# FPGA_01.net
KiCad netlist of a schematic drawn in Altium Designer
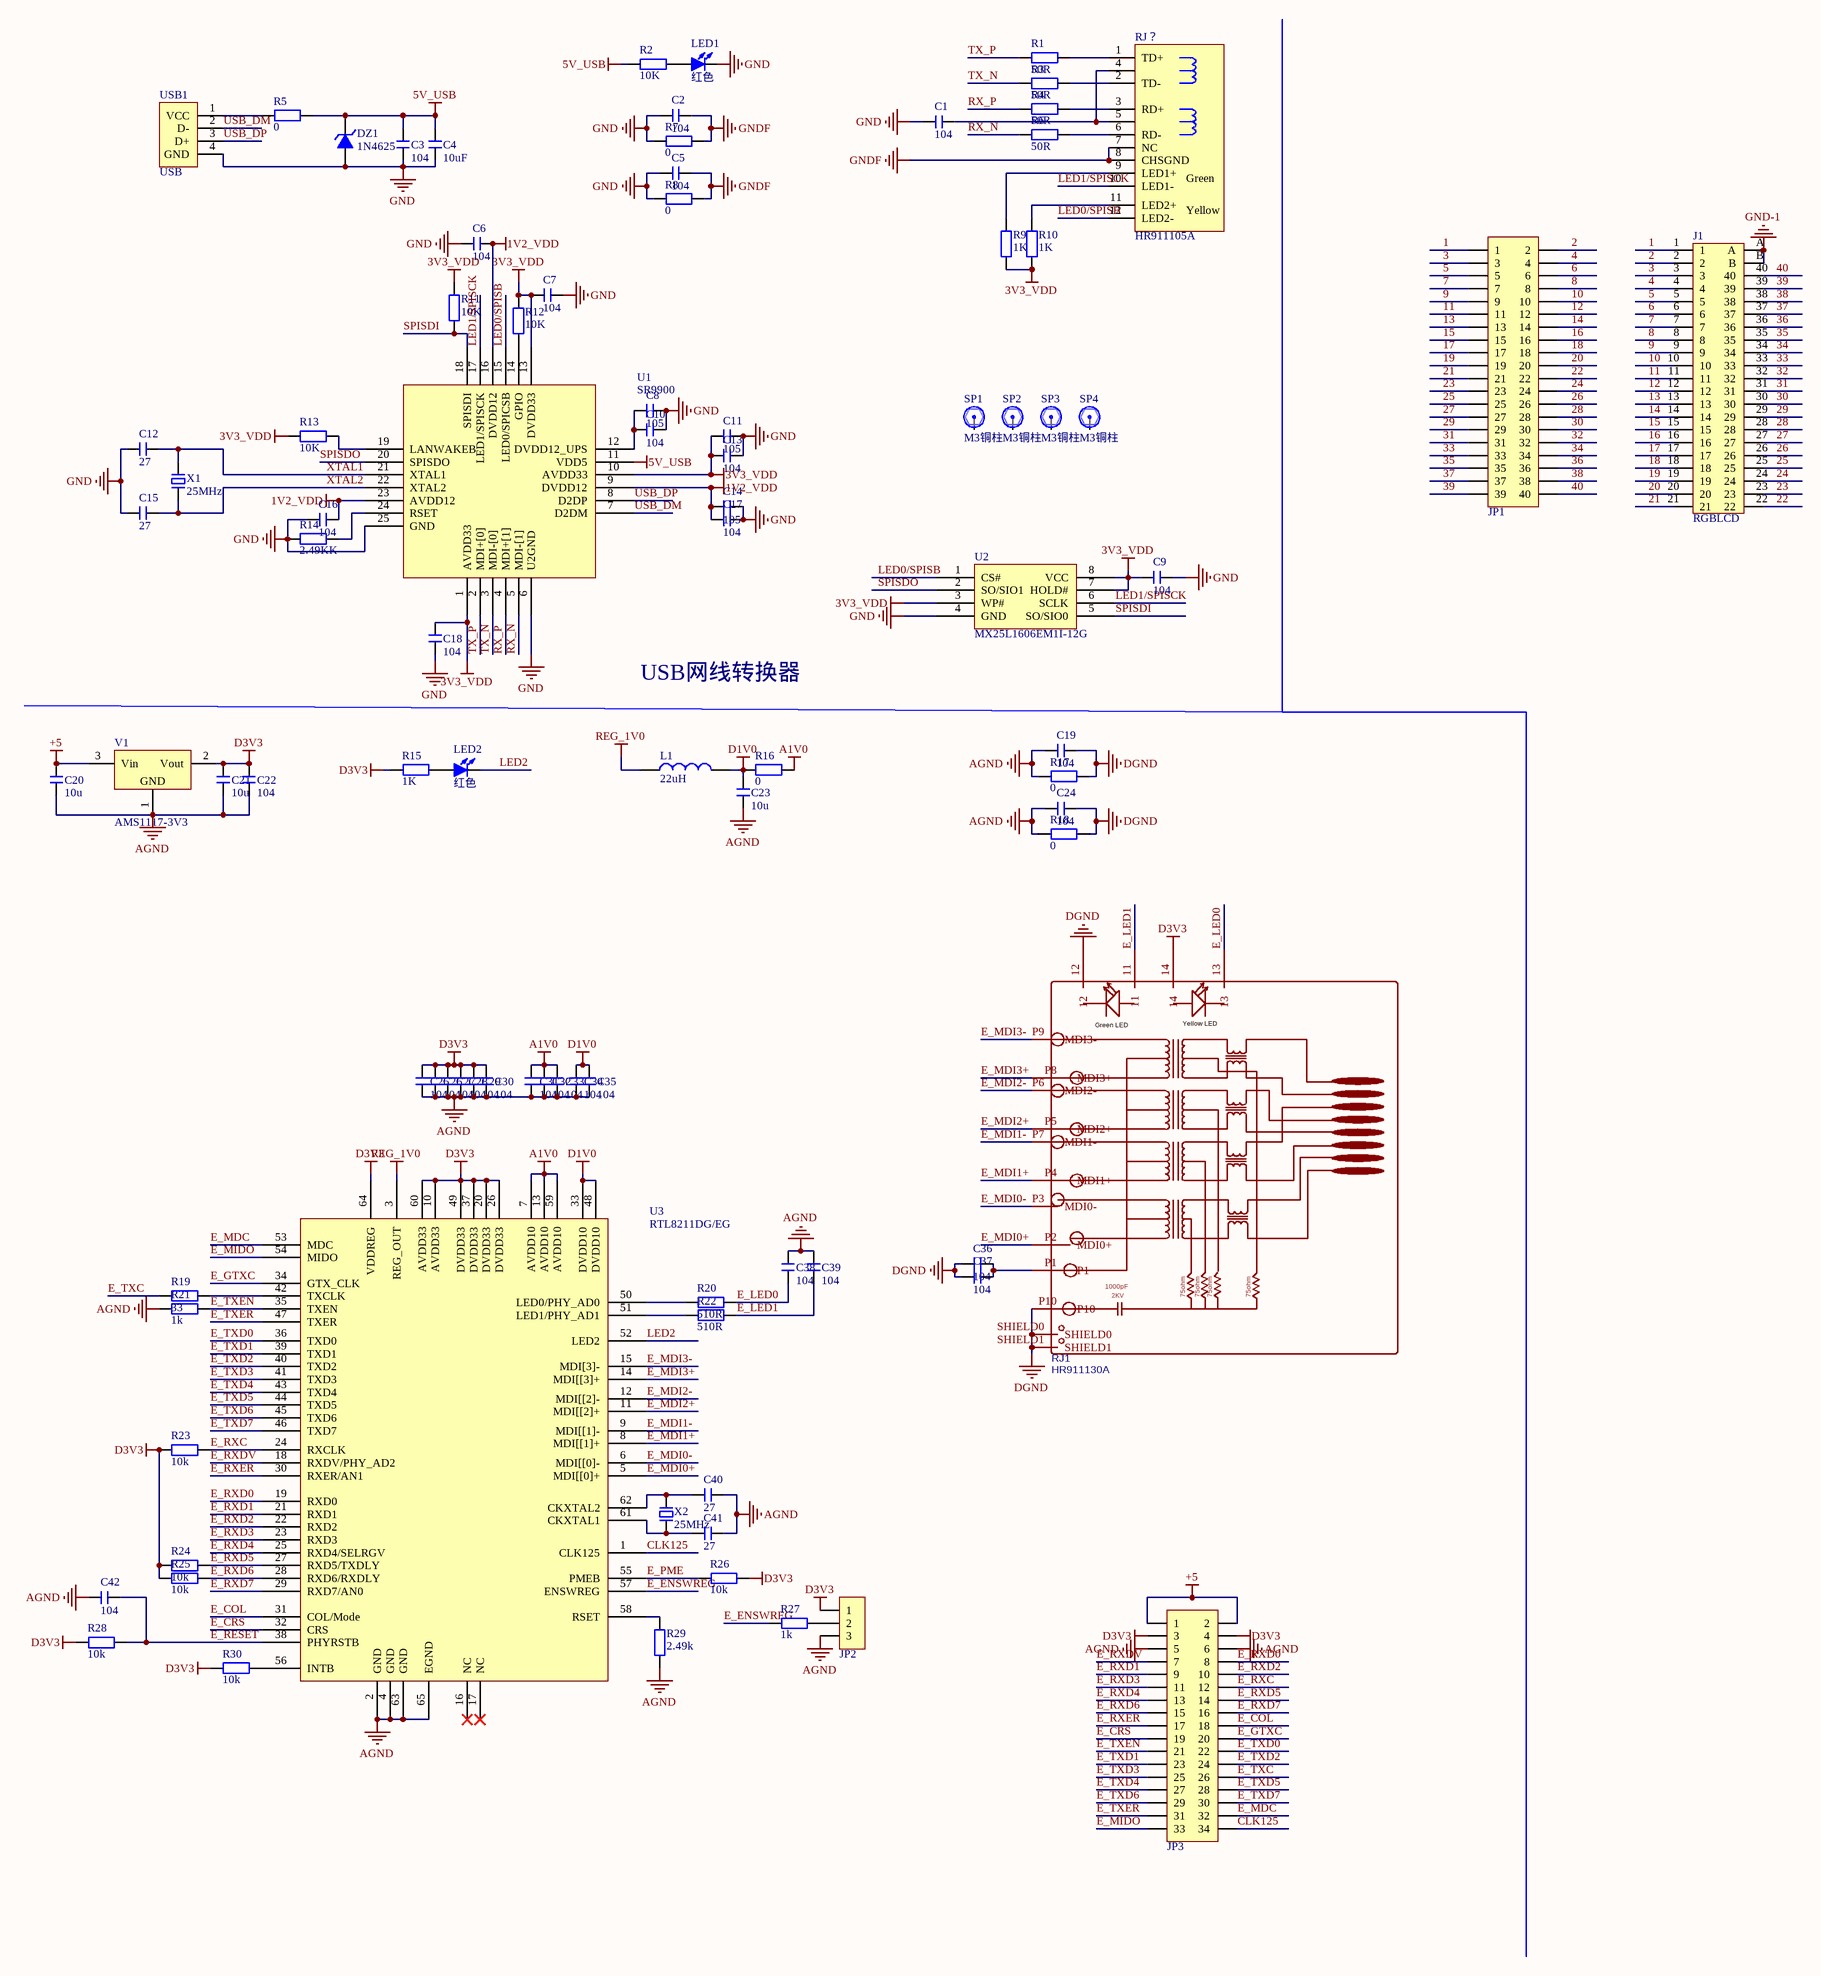
[diagram p0: FPGA扩展板01.SchDoc]

(export (version "E")
  (design (tool "Eeschema 10.0.6"))
  (components
    (comp (ref "C1")
      (value "104")
      (footprint "C 0805_L")
      (description "贴片电容")
      (libsource (lib "0.1 - 电阻-电容-电感") (part "C"))
    )
    (comp (ref "C2")
      (value "104")
      (footprint "C 0805_L")
      (description "贴片电容")
      (libsource (lib "0.1 - 电阻-电容-电感") (part "C"))
    )
    (comp (ref "C3")
      (value "104")
      (footprint "C 0805_L")
      (description "贴片电容")
      (libsource (lib "0.1 - 电阻-电容-电感") (part "C"))
    )
    (comp (ref "C4")
      (value "10uF")
      (footprint "C 0805_L")
      (description "贴片电容")
      (libsource (lib "0.1 - 电阻-电容-电感") (part "C"))
    )
    (comp (ref "C5")
      (value "104")
      (footprint "C 0805_L")
      (description "贴片电容")
      (libsource (lib "0.1 - 电阻-电容-电感") (part "C"))
    )
    (comp (ref "C6")
      (value "104")
      (footprint "C 0805_L")
      (description "贴片电容")
      (libsource (lib "0.1 - 电阻-电容-电感") (part "C"))
    )
    (comp (ref "C7")
      (value "104")
      (footprint "C 0805_L")
      (description "贴片电容")
      (libsource (lib "0.1 - 电阻-电容-电感") (part "C"))
    )
    (comp (ref "C8")
      (value "105")
      (footprint "C 0805_L")
      (description "贴片电容")
      (libsource (lib "0.1 - 电阻-电容-电感") (part "C"))
    )
    (comp (ref "C9")
      (value "104")
      (footprint "C 0805_L")
      (description "贴片电容")
      (libsource (lib "0.1 - 电阻-电容-电感") (part "C"))
    )
    (comp (ref "C10")
      (value "104")
      (footprint "C 0805_L")
      (description "贴片电容")
      (libsource (lib "0.1 - 电阻-电容-电感") (part "C"))
    )
    (comp (ref "C11")
      (value "105")
      (footprint "C 0805_L")
      (description "贴片电容")
      (libsource (lib "0.1 - 电阻-电容-电感") (part "C"))
    )
    (comp (ref "C12")
      (value "27")
      (footprint "C 0805_L")
      (description "贴片电容")
      (libsource (lib "0.1 - 电阻-电容-电感") (part "C"))
    )
    (comp (ref "C13")
      (value "104")
      (footprint "C 0805_L")
      (description "贴片电容")
      (libsource (lib "0.1 - 电阻-电容-电感") (part "C"))
    )
    (comp (ref "C14")
      (value "105")
      (footprint "C 0805_L")
      (description "贴片电容")
      (libsource (lib "0.1 - 电阻-电容-电感") (part "C"))
    )
    (comp (ref "C15")
      (value "27")
      (footprint "C 0805_L")
      (description "贴片电容")
      (libsource (lib "0.1 - 电阻-电容-电感") (part "C"))
    )
    (comp (ref "C16")
      (value "104")
      (footprint "C 0805_L")
      (description "贴片电容")
      (libsource (lib "0.1 - 电阻-电容-电感") (part "C"))
    )
    (comp (ref "C17")
      (value "104")
      (footprint "C 0805_L")
      (description "贴片电容")
      (libsource (lib "0.1 - 电阻-电容-电感") (part "C"))
    )
    (comp (ref "C18")
      (value "104")
      (footprint "C 0805_L")
      (description "贴片电容")
      (libsource (lib "0.1 - 电阻-电容-电感") (part "C"))
    )
    (comp (ref "C19")
      (value "104")
      (footprint "C 0805_L")
      (description "贴片电容")
      (libsource (lib "0.1 - 电阻-电容-电感") (part "C"))
    )
    (comp (ref "C20")
      (value "10u")
      (footprint "C 0805_L")
      (description "贴片电容")
      (libsource (lib "0.1 - 电阻-电容-电感") (part "C"))
    )
    (comp (ref "C21")
      (value "10u")
      (footprint "C 0805_L")
      (description "贴片电容")
      (libsource (lib "0.1 - 电阻-电容-电感") (part "C"))
    )
    (comp (ref "C22")
      (value "104")
      (footprint "C 0805_L")
      (description "贴片电容")
      (libsource (lib "0.1 - 电阻-电容-电感") (part "C"))
    )
    (comp (ref "C23")
      (value "10u")
      (footprint "C 0805_L")
      (description "贴片电容")
      (libsource (lib "0.1 - 电阻-电容-电感") (part "C"))
    )
    (comp (ref "C24")
      (value "104")
      (footprint "C 0805_L")
      (description "贴片电容")
      (libsource (lib "0.1 - 电阻-电容-电感") (part "C"))
    )
    (comp (ref "C25")
      (value "104")
      (footprint "C 0805_L")
      (description "贴片电容")
      (libsource (lib "0.1 - 电阻-电容-电感") (part "C"))
    )
    (comp (ref "C26")
      (value "104")
      (footprint "C 0805_L")
      (description "贴片电容")
      (libsource (lib "0.1 - 电阻-电容-电感") (part "C"))
    )
    (comp (ref "C27")
      (value "104")
      (footprint "C 0805_L")
      (description "贴片电容")
      (libsource (lib "0.1 - 电阻-电容-电感") (part "C"))
    )
    (comp (ref "C28")
      (value "104")
      (footprint "C 0805_L")
      (description "贴片电容")
      (libsource (lib "0.1 - 电阻-电容-电感") (part "C"))
    )
    (comp (ref "C29")
      (value "104")
      (footprint "C 0805_L")
      (description "贴片电容")
      (libsource (lib "0.1 - 电阻-电容-电感") (part "C"))
    )
    (comp (ref "C30")
      (value "104")
      (footprint "C 0805_L")
      (description "贴片电容")
      (libsource (lib "0.1 - 电阻-电容-电感") (part "C"))
    )
    (comp (ref "C31")
      (value "104")
      (footprint "C 0805_L")
      (description "贴片电容")
      (libsource (lib "0.1 - 电阻-电容-电感") (part "C"))
    )
    (comp (ref "C32")
      (value "104")
      (footprint "C 0805_L")
      (description "贴片电容")
      (libsource (lib "0.1 - 电阻-电容-电感") (part "C"))
    )
    (comp (ref "C33")
      (value "104")
      (footprint "C 0805_L")
      (description "贴片电容")
      (libsource (lib "0.1 - 电阻-电容-电感") (part "C"))
    )
    (comp (ref "C34")
      (value "104")
      (footprint "C 0805_L")
      (description "贴片电容")
      (libsource (lib "0.1 - 电阻-电容-电感") (part "C"))
    )
    (comp (ref "C35")
      (value "104")
      (footprint "C 0805_L")
      (description "贴片电容")
      (libsource (lib "0.1 - 电阻-电容-电感") (part "C"))
    )
    (comp (ref "C36")
      (value "104")
      (footprint "C 0805_L")
      (description "贴片电容")
      (libsource (lib "0.1 - 电阻-电容-电感") (part "C"))
    )
    (comp (ref "C37")
      (value "104")
      (footprint "C 0805_L")
      (description "贴片电容")
      (libsource (lib "0.1 - 电阻-电容-电感") (part "C"))
    )
    (comp (ref "C38")
      (value "104")
      (footprint "C 0805_L")
      (description "贴片电容")
      (libsource (lib "0.1 - 电阻-电容-电感") (part "C"))
    )
    (comp (ref "C39")
      (value "104")
      (footprint "C 0805_L")
      (description "贴片电容")
      (libsource (lib "0.1 - 电阻-电容-电感") (part "C"))
    )
    (comp (ref "C40")
      (value "27")
      (footprint "C 0805_L")
      (description "贴片电容")
      (libsource (lib "0.1 - 电阻-电容-电感") (part "C"))
    )
    (comp (ref "C41")
      (value "27")
      (footprint "C 0805_L")
      (description "贴片电容")
      (libsource (lib "0.1 - 电阻-电容-电感") (part "C"))
    )
    (comp (ref "C42")
      (value "104")
      (footprint "C 0805_L")
      (description "贴片电容")
      (libsource (lib "0.1 - 电阻-电容-电感") (part "C"))
    )
    (comp (ref "DZ1")
      (value "1N4625")
      (footprint "DO-35")
      (description "5.1V/0.5W稳压管")
      (libsource (lib "0.2 -  二极管-整流桥") (part "1N4625"))
    )
    (comp (ref "J1")
      (value "RGBLCD")
      (footprint "FPC-TOP40")
      (description "FPC-40P-0.5mm")
      (libsource (lib "PIONEER") (part "FPC-40"))
    )
    (comp (ref "JP1")
      (value "Header 2X11")
      (footprint "HDR2.54-LI-2x20P")
      (description "20*2P接插件")
      (libsource (lib "5.3 - 接插件-脚距2.54 (100mil) ") (part "Header 20X2"))
    )
    (comp (ref "JP2")
      (value "HDR-1X3")
      (footprint "HDR2.54-LI-3P")
      (description "3P接插件")
      (libsource (lib "5.3 - 接插件-脚距2.54 (100mil) ") (part "Header 3"))
    )
    (comp (ref "JP3")
      (value "Header 2X11")
      (footprint "HDR2.54-LI-2x17P")
      (description "17*2P接插件")
      (libsource (lib "5.3 - 接插件-脚距2.54 (100mil) ") (part "Header 17X2"))
    )
    (comp (ref "L1")
      (value "22uH")
      (footprint "L 0805")
      (description "小功率贴片电感")
      (libsource (lib "0.1 - 电阻-电容-电感") (part "L"))
    )
    (comp (ref "LED1")
      (value "红色")
      (footprint "LED 0805G")
      (description "贴片LED")
      (libsource (lib "0.3 - LED发光二极管") (part "LED-SMD"))
    )
    (comp (ref "LED2")
      (value "红色")
      (footprint "LED 0805G")
      (description "贴片LED")
      (libsource (lib "0.3 - LED发光二极管") (part "LED-SMD"))
    )
    (comp (ref "R1")
      (value "50R")
      (footprint "R 0805_L")
      (description "贴片电阻")
      (libsource (lib "0.1 - 电阻-电容-电感") (part "R"))
    )
    (comp (ref "R2")
      (value "10K")
      (footprint "R 0805_L")
      (description "贴片电阻")
      (libsource (lib "0.1 - 电阻-电容-电感") (part "R"))
    )
    (comp (ref "R3")
      (value "50R")
      (footprint "R 0805_L")
      (description "贴片电阻")
      (libsource (lib "0.1 - 电阻-电容-电感") (part "R"))
    )
    (comp (ref "R4")
      (value "50R")
      (footprint "R 0805_L")
      (description "贴片电阻")
      (libsource (lib "0.1 - 电阻-电容-电感") (part "R"))
    )
    (comp (ref "R5")
      (value "0")
      (footprint "R 0805_L")
      (description "贴片电阻")
      (libsource (lib "0.1 - 电阻-电容-电感") (part "R"))
    )
    (comp (ref "R6")
      (value "50R")
      (footprint "R 0805_L")
      (description "贴片电阻")
      (libsource (lib "0.1 - 电阻-电容-电感") (part "R"))
    )
    (comp (ref "R7")
      (value "0")
      (footprint "R 0805_L")
      (description "贴片电阻")
      (libsource (lib "0.1 - 电阻-电容-电感") (part "R"))
    )
    (comp (ref "R8")
      (value "0")
      (footprint "R 0805_L")
      (description "贴片电阻")
      (libsource (lib "0.1 - 电阻-电容-电感") (part "R"))
    )
    (comp (ref "R9")
      (value "1K")
      (footprint "R 0805_L")
      (description "贴片电阻")
      (libsource (lib "0.1 - 电阻-电容-电感") (part "R"))
    )
    (comp (ref "R10")
      (value "1K")
      (footprint "R 0805_L")
      (description "贴片电阻")
      (libsource (lib "0.1 - 电阻-电容-电感") (part "R"))
    )
    (comp (ref "R11")
      (value "10K")
      (footprint "R 0805_L")
      (description "贴片电阻")
      (libsource (lib "0.1 - 电阻-电容-电感") (part "R"))
    )
    (comp (ref "R12")
      (value "10K")
      (footprint "R 0805_L")
      (description "贴片电阻")
      (libsource (lib "0.1 - 电阻-电容-电感") (part "R"))
    )
    (comp (ref "R13")
      (value "10K")
      (footprint "R 0805_L")
      (description "贴片电阻")
      (libsource (lib "0.1 - 电阻-电容-电感") (part "R"))
    )
    (comp (ref "R14")
      (value "2.49KK")
      (footprint "R 0805_L")
      (description "贴片电阻")
      (libsource (lib "0.1 - 电阻-电容-电感") (part "R"))
    )
    (comp (ref "R15")
      (value "1K")
      (footprint "R 0805_L")
      (description "贴片电阻")
      (libsource (lib "0.1 - 电阻-电容-电感") (part "R"))
    )
    (comp (ref "R16")
      (value "0")
      (footprint "R 0805_L")
      (description "贴片电阻")
      (libsource (lib "0.1 - 电阻-电容-电感") (part "R"))
    )
    (comp (ref "R17")
      (value "0")
      (footprint "R 0805_L")
      (description "贴片电阻")
      (libsource (lib "0.1 - 电阻-电容-电感") (part "R"))
    )
    (comp (ref "R18")
      (value "0")
      (footprint "R 0805_L")
      (description "贴片电阻")
      (libsource (lib "0.1 - 电阻-电容-电感") (part "R"))
    )
    (comp (ref "R19")
      (value "33")
      (footprint "R 0805_L")
      (description "贴片电阻")
      (libsource (lib "0.1 - 电阻-电容-电感") (part "R"))
    )
    (comp (ref "R20")
      (value "510R")
      (footprint "R 0805_L")
      (description "贴片电阻")
      (libsource (lib "0.1 - 电阻-电容-电感") (part "R"))
    )
    (comp (ref "R21")
      (value "1k")
      (footprint "R 0805_L")
      (description "贴片电阻")
      (libsource (lib "0.1 - 电阻-电容-电感") (part "R"))
    )
    (comp (ref "R22")
      (value "510R")
      (footprint "R 0805_L")
      (description "贴片电阻")
      (libsource (lib "0.1 - 电阻-电容-电感") (part "R"))
    )
    (comp (ref "R23")
      (value "10k")
      (footprint "R 0805_L")
      (description "贴片电阻")
      (libsource (lib "0.1 - 电阻-电容-电感") (part "R"))
    )
    (comp (ref "R24")
      (value "10k")
      (footprint "R 0805_L")
      (description "贴片电阻")
      (libsource (lib "0.1 - 电阻-电容-电感") (part "R"))
    )
    (comp (ref "R25")
      (value "10k")
      (footprint "R 0805_L")
      (description "贴片电阻")
      (libsource (lib "0.1 - 电阻-电容-电感") (part "R"))
    )
    (comp (ref "R26")
      (value "10k")
      (footprint "R 0805_L")
      (description "贴片电阻")
      (libsource (lib "0.1 - 电阻-电容-电感") (part "R"))
    )
    (comp (ref "R27")
      (value "1k")
      (footprint "R 0805_L")
      (description "贴片电阻")
      (libsource (lib "0.1 - 电阻-电容-电感") (part "R"))
    )
    (comp (ref "R28")
      (value "10k")
      (footprint "R 0805_L")
      (description "贴片电阻")
      (libsource (lib "0.1 - 电阻-电容-电感") (part "R"))
    )
    (comp (ref "R29")
      (value "2.49k")
      (footprint "R 0805_L")
      (description "贴片电阻")
      (libsource (lib "0.1 - 电阻-电容-电感") (part "R"))
    )
    (comp (ref "R30")
      (value "10k")
      (footprint "R 0805_L")
      (description "贴片电阻")
      (libsource (lib "0.1 - 电阻-电容-电感") (part "R"))
    )
    (comp (ref "RJ1")
      (value "HR911130A")
      (footprint "RJ_45")
      (description "RJ_45网口")
      (fields (field (name "BOM_SUPPLIER PART") "C54408"))
      (libsource (lib "Schlib1") (part "HR911130A"))
    )
    (comp (ref "RJ？")
      (value "HR911105A")
      (footprint "RJ-45A12")
      (description "带灯以太网接口")
      (libsource (lib "0.8 - 网口-音频插座") (part "HR911105A"))
    )
    (comp (ref "SP1")
      (value "M3铜柱")
      (footprint "M3x10+6_L")
      (description "铜柱")
      (libsource (lib "4.1 - 未分类器件") (part "铜柱加头小焊盘"))
    )
    (comp (ref "SP2")
      (value "M3铜柱")
      (footprint "M3x10+6_L")
      (description "铜柱")
      (libsource (lib "4.1 - 未分类器件") (part "铜柱加头小焊盘"))
    )
    (comp (ref "SP3")
      (value "M3铜柱")
      (footprint "M3x10+6_L")
      (description "铜柱")
      (libsource (lib "4.1 - 未分类器件") (part "铜柱加头小焊盘"))
    )
    (comp (ref "SP4")
      (value "M3铜柱")
      (footprint "M3x10+6_L")
      (description "铜柱")
      (libsource (lib "4.1 - 未分类器件") (part "铜柱加头小焊盘"))
    )
    (comp (ref "U1") (value "SR9900") (footprint "QFN24 4x4_M") (libsource (lib "Schlib1") (part "SR9900")))
    (comp (ref "U2")
      (value "MX25L1606EM1I-12G")
      (footprint "SOP8W_N")
      (libsource (lib "Schlib1") (part "MX25L1606EM1I-12G"))
    )
    (comp (ref "U3")
      (value "RTL8211DG/EG")
      (footprint "QFN65-050-0909")
      (libsource (lib "Schlib1") (part "RTL8211DG/EG"))
    )
    (comp (ref "USB1")
      (value "USB")
      (footprint "USB_A/P_A")
      (description "USB-A型公接口")
      (libsource (lib "0.8 - 网口-音频插座") (part "USB-A/P"))
    )
    (comp (ref "V1")
      (value "AMS1117-3V3")
      (footprint "SOT223_L")
      (description "三端稳压芯片")
      (libsource (lib "1.1 - 电源类芯片") (part "AMS1117"))
    )
    (comp (ref "X1")
      (value "25MHz")
      (footprint "OSC HC-49S")
      (description "2脚无源脚晶振")
      (libsource (lib "2.0 - 保险丝-晶振-光耦") (part "XTAL-2P"))
    )
    (comp (ref "X2")
      (value "25MHz")
      (footprint "OSC HC-49S")
      (description "2脚无源脚晶振")
      (libsource (lib "2.0 - 保险丝-晶振-光耦") (part "XTAL-2P"))
    )
  )
  (nets
    (net (code "1") (name "+5") (class "Default")
      (node (ref "C20") (pin "2") (pinfunction "2_2") (pintype "passive"))
      (node (ref "JP3") (pin "1") (pinfunction "1_1") (pintype "passive"))
      (node (ref "JP3") (pin "2") (pinfunction "2_2") (pintype "passive"))
      (node (ref "V1") (pin "3") (pinfunction "Vin_3") (pintype "passive"))
    )
    (net (code "2") (name "/1") (class "Default")
      (node (ref "J1") (pin "1") (pinfunction "1_1") (pintype "passive"))
      (node (ref "JP1") (pin "1") (pinfunction "1_1") (pintype "passive"))
    )
    (net (code "3") (name "/2") (class "Default")
      (node (ref "J1") (pin "2") (pinfunction "2_2") (pintype "passive"))
      (node (ref "JP1") (pin "2") (pinfunction "2_2") (pintype "passive"))
    )
    (net (code "4") (name "/3") (class "Default")
      (node (ref "J1") (pin "3") (pinfunction "3_3") (pintype "passive"))
      (node (ref "JP1") (pin "3") (pinfunction "3_3") (pintype "passive"))
    )
    (net (code "5") (name "/4") (class "Default")
      (node (ref "J1") (pin "4") (pinfunction "4_4") (pintype "passive"))
      (node (ref "JP1") (pin "4") (pinfunction "4_4") (pintype "passive"))
    )
    (net (code "6") (name "/5") (class "Default")
      (node (ref "J1") (pin "5") (pinfunction "5_5") (pintype "passive"))
      (node (ref "JP1") (pin "5") (pinfunction "5_5") (pintype "passive"))
    )
    (net (code "7") (name "/6") (class "Default")
      (node (ref "J1") (pin "6") (pinfunction "6_6") (pintype "passive"))
      (node (ref "JP1") (pin "6") (pinfunction "6_6") (pintype "passive"))
    )
    (net (code "8") (name "/7") (class "Default")
      (node (ref "J1") (pin "7") (pinfunction "7_7") (pintype "passive"))
      (node (ref "JP1") (pin "7") (pinfunction "7_7") (pintype "passive"))
    )
    (net (code "9") (name "/8") (class "Default")
      (node (ref "J1") (pin "8") (pinfunction "8_8") (pintype "passive"))
      (node (ref "JP1") (pin "8") (pinfunction "8_8") (pintype "passive"))
    )
    (net (code "10") (name "/9") (class "Default")
      (node (ref "J1") (pin "9") (pinfunction "9_9") (pintype "passive"))
      (node (ref "JP1") (pin "9") (pinfunction "9_9") (pintype "passive"))
    )
    (net (code "11") (name "/10") (class "Default")
      (node (ref "J1") (pin "10") (pinfunction "10_10") (pintype "passive"))
      (node (ref "JP1") (pin "10") (pinfunction "10_10") (pintype "passive"))
    )
    (net (code "12") (name "/11") (class "Default")
      (node (ref "J1") (pin "11") (pinfunction "11_11") (pintype "passive"))
      (node (ref "JP1") (pin "11") (pinfunction "11_11") (pintype "passive"))
    )
    (net (code "13") (name "/12") (class "Default")
      (node (ref "J1") (pin "12") (pinfunction "12_12") (pintype "passive"))
      (node (ref "JP1") (pin "12") (pinfunction "12_12") (pintype "passive"))
    )
    (net (code "14") (name "/13") (class "Default")
      (node (ref "J1") (pin "13") (pinfunction "13_13") (pintype "passive"))
      (node (ref "JP1") (pin "13") (pinfunction "13_13") (pintype "passive"))
    )
    (net (code "15") (name "/14") (class "Default")
      (node (ref "J1") (pin "14") (pinfunction "14_14") (pintype "passive"))
      (node (ref "JP1") (pin "14") (pinfunction "14_14") (pintype "passive"))
    )
    (net (code "16") (name "/15") (class "Default")
      (node (ref "J1") (pin "15") (pinfunction "15_15") (pintype "passive"))
      (node (ref "JP1") (pin "15") (pinfunction "15_15") (pintype "passive"))
    )
    (net (code "17") (name "/16") (class "Default")
      (node (ref "J1") (pin "16") (pinfunction "16_16") (pintype "passive"))
      (node (ref "JP1") (pin "16") (pinfunction "16_16") (pintype "passive"))
    )
    (net (code "18") (name "/17") (class "Default")
      (node (ref "J1") (pin "17") (pinfunction "17_17") (pintype "passive"))
      (node (ref "JP1") (pin "17") (pinfunction "17_17") (pintype "passive"))
    )
    (net (code "19") (name "/18") (class "Default")
      (node (ref "J1") (pin "18") (pinfunction "18_18") (pintype "passive"))
      (node (ref "JP1") (pin "18") (pinfunction "18_18") (pintype "passive"))
    )
    (net (code "20") (name "/19") (class "Default")
      (node (ref "J1") (pin "19") (pinfunction "19_19") (pintype "passive"))
      (node (ref "JP1") (pin "19") (pinfunction "19_19") (pintype "passive"))
    )
    (net (code "21") (name "/20") (class "Default")
      (node (ref "J1") (pin "20") (pinfunction "20_20") (pintype "passive"))
      (node (ref "JP1") (pin "20") (pinfunction "20_20") (pintype "passive"))
    )
    (net (code "22") (name "/21") (class "Default")
      (node (ref "J1") (pin "21") (pinfunction "21_21") (pintype "passive"))
      (node (ref "JP1") (pin "21") (pinfunction "21_21") (pintype "passive"))
    )
    (net (code "23") (name "/22") (class "Default")
      (node (ref "J1") (pin "22") (pinfunction "22_22") (pintype "passive"))
      (node (ref "JP1") (pin "22") (pinfunction "22_22") (pintype "passive"))
    )
    (net (code "24") (name "/23") (class "Default")
      (node (ref "J1") (pin "23") (pinfunction "23_23") (pintype "passive"))
      (node (ref "JP1") (pin "23") (pinfunction "23_23") (pintype "passive"))
    )
    (net (code "25") (name "/24") (class "Default")
      (node (ref "J1") (pin "24") (pinfunction "24_24") (pintype "passive"))
      (node (ref "JP1") (pin "24") (pinfunction "24_24") (pintype "passive"))
    )
    (net (code "26") (name "/25") (class "Default")
      (node (ref "J1") (pin "25") (pinfunction "25_25") (pintype "passive"))
      (node (ref "JP1") (pin "25") (pinfunction "25_25") (pintype "passive"))
    )
    (net (code "27") (name "/26") (class "Default")
      (node (ref "J1") (pin "26") (pinfunction "26_26") (pintype "passive"))
      (node (ref "JP1") (pin "26") (pinfunction "26_26") (pintype "passive"))
    )
    (net (code "28") (name "/27") (class "Default")
      (node (ref "J1") (pin "27") (pinfunction "27_27") (pintype "passive"))
      (node (ref "JP1") (pin "27") (pinfunction "27_27") (pintype "passive"))
    )
    (net (code "29") (name "/28") (class "Default")
      (node (ref "J1") (pin "28") (pinfunction "28_28") (pintype "passive"))
      (node (ref "JP1") (pin "28") (pinfunction "28_28") (pintype "passive"))
    )
    (net (code "30") (name "/29") (class "Default")
      (node (ref "J1") (pin "29") (pinfunction "29_29") (pintype "passive"))
      (node (ref "JP1") (pin "29") (pinfunction "29_29") (pintype "passive"))
    )
    (net (code "31") (name "/30") (class "Default")
      (node (ref "J1") (pin "30") (pinfunction "30_30") (pintype "passive"))
      (node (ref "JP1") (pin "30") (pinfunction "30_30") (pintype "passive"))
    )
    (net (code "32") (name "/31") (class "Default")
      (node (ref "J1") (pin "31") (pinfunction "31_31") (pintype "passive"))
      (node (ref "JP1") (pin "31") (pinfunction "31_31") (pintype "passive"))
    )
    (net (code "33") (name "/32") (class "Default")
      (node (ref "J1") (pin "32") (pinfunction "32_32") (pintype "passive"))
      (node (ref "JP1") (pin "32") (pinfunction "32_32") (pintype "passive"))
    )
    (net (code "34") (name "/33") (class "Default")
      (node (ref "J1") (pin "33") (pinfunction "33_33") (pintype "passive"))
      (node (ref "JP1") (pin "33") (pinfunction "33_33") (pintype "passive"))
    )
    (net (code "35") (name "/34") (class "Default")
      (node (ref "J1") (pin "34") (pinfunction "34_34") (pintype "passive"))
      (node (ref "JP1") (pin "34") (pinfunction "34_34") (pintype "passive"))
    )
    (net (code "36") (name "/35") (class "Default")
      (node (ref "J1") (pin "35") (pinfunction "35_35") (pintype "passive"))
      (node (ref "JP1") (pin "35") (pinfunction "35_35") (pintype "passive"))
    )
    (net (code "37") (name "/36") (class "Default")
      (node (ref "J1") (pin "36") (pinfunction "36_36") (pintype "passive"))
      (node (ref "JP1") (pin "36") (pinfunction "36_36") (pintype "passive"))
    )
    (net (code "38") (name "/37") (class "Default")
      (node (ref "J1") (pin "37") (pinfunction "37_37") (pintype "passive"))
      (node (ref "JP1") (pin "37") (pinfunction "37_37") (pintype "passive"))
    )
    (net (code "39") (name "/38") (class "Default")
      (node (ref "J1") (pin "38") (pinfunction "38_38") (pintype "passive"))
      (node (ref "JP1") (pin "38") (pinfunction "38_38") (pintype "passive"))
    )
    (net (code "40") (name "/39") (class "Default")
      (node (ref "J1") (pin "39") (pinfunction "39_39") (pintype "passive"))
      (node (ref "JP1") (pin "39") (pinfunction "39_39") (pintype "passive"))
    )
    (net (code "41") (name "/40") (class "Default")
      (node (ref "J1") (pin "40") (pinfunction "40_40") (pintype "passive"))
      (node (ref "JP1") (pin "40") (pinfunction "40_40") (pintype "passive"))
    )
    (net (code "42") (name "/CLK125") (class "Default")
      (node (ref "JP3") (pin "34") (pinfunction "34_34") (pintype "passive"))
      (node (ref "U3") (pin "1") (pinfunction "CLK125_1") (pintype "passive"))
    )
    (net (code "43") (name "/E_COL") (class "Default")
      (node (ref "JP3") (pin "18") (pinfunction "18_18") (pintype "passive"))
      (node (ref "U3") (pin "31") (pinfunction "COL/Mode_31") (pintype "passive"))
    )
    (net (code "44") (name "/E_CRS") (class "Default")
      (node (ref "JP3") (pin "19") (pinfunction "19_19") (pintype "passive"))
      (node (ref "U3") (pin "32") (pinfunction "CRS_32") (pintype "passive"))
    )
    (net (code "45") (name "/E_ENSWREG") (class "Default")
      (node (ref "R27") (pin "2") (pinfunction "2_2") (pintype "passive"))
      (node (ref "U3") (pin "57") (pinfunction "ENSWREG_57") (pintype "passive"))
    )
    (net (code "46") (name "/E_GTXC") (class "Default")
      (node (ref "JP3") (pin "20") (pinfunction "20_20") (pintype "passive"))
      (node (ref "U3") (pin "34") (pinfunction "GTX_CLK_34") (pintype "passive"))
    )
    (net (code "47") (name "/E_LED0") (class "Default")
      (node (ref "C38") (pin "1") (pinfunction "1_1") (pintype "passive"))
      (node (ref "R20") (pin "2") (pinfunction "2_2") (pintype "passive"))
      (node (ref "RJ1") (pin "13") (pinfunction "13_13") (pintype "passive"))
    )
    (net (code "48") (name "/E_LED1") (class "Default")
      (node (ref "C39") (pin "1") (pinfunction "1_1") (pintype "passive"))
      (node (ref "R22") (pin "2") (pinfunction "2_2") (pintype "passive"))
      (node (ref "RJ1") (pin "11") (pinfunction "11_11") (pintype "passive"))
    )
    (net (code "49") (name "/E_MDC") (class "Default")
      (node (ref "JP3") (pin "32") (pinfunction "32_32") (pintype "passive"))
      (node (ref "U3") (pin "53") (pinfunction "MDC_53") (pintype "passive"))
    )
    (net (code "50") (name "/E_MDI0+") (class "Default")
      (node (ref "RJ1") (pin "P2") (pinfunction "MDI0+_P2") (pintype "passive"))
      (node (ref "U3") (pin "5") (pinfunction "MDI[[0]+_5") (pintype "passive"))
    )
    (net (code "51") (name "/E_MDI0-") (class "Default")
      (node (ref "RJ1") (pin "P3") (pinfunction "MDI0-_P3") (pintype "passive"))
      (node (ref "U3") (pin "6") (pinfunction "MDI[[0]-_6") (pintype "passive"))
    )
    (net (code "52") (name "/E_MDI1+") (class "Default")
      (node (ref "RJ1") (pin "P4") (pinfunction "MDI1+_P4") (pintype "passive"))
      (node (ref "U3") (pin "8") (pinfunction "MDI[[1]+_8") (pintype "passive"))
    )
    (net (code "53") (name "/E_MDI1-") (class "Default")
      (node (ref "RJ1") (pin "P7") (pinfunction "MDI1-_P7") (pintype "passive"))
      (node (ref "U3") (pin "9") (pinfunction "MDI[[1]-_9") (pintype "passive"))
    )
    (net (code "54") (name "/E_MDI2+") (class "Default")
      (node (ref "RJ1") (pin "P5") (pinfunction "MDI2+_P5") (pintype "passive"))
      (node (ref "U3") (pin "11") (pinfunction "MDI[[2]+_11") (pintype "passive"))
    )
    (net (code "55") (name "/E_MDI2-") (class "Default")
      (node (ref "RJ1") (pin "P6") (pinfunction "MDI2-_P6") (pintype "passive"))
      (node (ref "U3") (pin "12") (pinfunction "MDI[[2]-_12") (pintype "passive"))
    )
    (net (code "56") (name "/E_MDI3+") (class "Default")
      (node (ref "RJ1") (pin "P8") (pinfunction "MDI3+_P8") (pintype "passive"))
      (node (ref "U3") (pin "14") (pinfunction "MDI[[3]+_14") (pintype "passive"))
    )
    (net (code "57") (name "/E_MDI3-") (class "Default")
      (node (ref "RJ1") (pin "P9") (pinfunction "MDI3-_P9") (pintype "passive"))
      (node (ref "U3") (pin "15") (pinfunction "MDI[3]-_15") (pintype "passive"))
    )
    (net (code "58") (name "/E_MIDO") (class "Default")
      (node (ref "JP3") (pin "33") (pinfunction "33_33") (pintype "passive"))
      (node (ref "U3") (pin "54") (pinfunction "MIDO_54") (pintype "passive"))
    )
    (net (code "59") (name "/E_PME") (class "Default")
      (node (ref "R26") (pin "2") (pinfunction "2_2") (pintype "passive"))
      (node (ref "U3") (pin "55") (pinfunction "PMEB_55") (pintype "passive"))
    )
    (net (code "60") (name "/E_RESET") (class "Default")
      (node (ref "C42") (pin "1") (pinfunction "1_1") (pintype "passive"))
      (node (ref "R28") (pin "2") (pinfunction "2_2") (pintype "passive"))
      (node (ref "U3") (pin "38") (pinfunction "PHYRSTB_38") (pintype "passive"))
    )
    (net (code "61") (name "/E_RXC") (class "Default")
      (node (ref "JP3") (pin "12") (pinfunction "12_12") (pintype "passive"))
      (node (ref "R23") (pin "2") (pinfunction "2_2") (pintype "passive"))
      (node (ref "U3") (pin "24") (pinfunction "RXCLK_24") (pintype "passive"))
    )
    (net (code "62") (name "/E_RXD0") (class "Default")
      (node (ref "JP3") (pin "8") (pinfunction "8_8") (pintype "passive"))
      (node (ref "U3") (pin "19") (pinfunction "RXD0_19") (pintype "passive"))
    )
    (net (code "63") (name "/E_RXD1") (class "Default")
      (node (ref "JP3") (pin "9") (pinfunction "9_9") (pintype "passive"))
      (node (ref "U3") (pin "21") (pinfunction "RXD1_21") (pintype "passive"))
    )
    (net (code "64") (name "/E_RXD2") (class "Default")
      (node (ref "JP3") (pin "10") (pinfunction "10_10") (pintype "passive"))
      (node (ref "U3") (pin "22") (pinfunction "RXD2_22") (pintype "passive"))
    )
    (net (code "65") (name "/E_RXD3") (class "Default")
      (node (ref "JP3") (pin "11") (pinfunction "11_11") (pintype "passive"))
      (node (ref "U3") (pin "23") (pinfunction "RXD3_23") (pintype "passive"))
    )
    (net (code "66") (name "/E_RXD4") (class "Default")
      (node (ref "JP3") (pin "13") (pinfunction "13_13") (pintype "passive"))
      (node (ref "U3") (pin "25") (pinfunction "RXD4/SELRGV_25") (pintype "passive"))
    )
    (net (code "67") (name "/E_RXD5") (class "Default")
      (node (ref "JP3") (pin "14") (pinfunction "14_14") (pintype "passive"))
      (node (ref "R24") (pin "2") (pinfunction "2_2") (pintype "passive"))
      (node (ref "U3") (pin "27") (pinfunction "RXD5/TXDLY_27") (pintype "passive"))
    )
    (net (code "68") (name "/E_RXD6") (class "Default")
      (node (ref "JP3") (pin "15") (pinfunction "15_15") (pintype "passive"))
      (node (ref "R25") (pin "2") (pinfunction "2_2") (pintype "passive"))
      (node (ref "U3") (pin "28") (pinfunction "RXD6/RXDLY_28") (pintype "passive"))
    )
    (net (code "69") (name "/E_RXD7") (class "Default")
      (node (ref "JP3") (pin "16") (pinfunction "16_16") (pintype "passive"))
      (node (ref "U3") (pin "29") (pinfunction "RXD7/AN0_29") (pintype "passive"))
    )
    (net (code "70") (name "/E_RXDV") (class "Default")
      (node (ref "JP3") (pin "7") (pinfunction "7_7") (pintype "passive"))
      (node (ref "U3") (pin "18") (pinfunction "RXDV/PHY_AD2_18") (pintype "passive"))
    )
    (net (code "71") (name "/E_RXER") (class "Default")
      (node (ref "JP3") (pin "17") (pinfunction "17_17") (pintype "passive"))
      (node (ref "U3") (pin "30") (pinfunction "RXER/AN1_30") (pintype "passive"))
    )
    (net (code "72") (name "/E_TXC") (class "Default")
      (node (ref "JP3") (pin "26") (pinfunction "26_26") (pintype "passive"))
      (node (ref "R19") (pin "1") (pinfunction "1_1") (pintype "passive"))
    )
    (net (code "73") (name "/E_TXD0") (class "Default")
      (node (ref "JP3") (pin "22") (pinfunction "22_22") (pintype "passive"))
      (node (ref "U3") (pin "36") (pinfunction "TXD0_36") (pintype "passive"))
    )
    (net (code "74") (name "/E_TXD1") (class "Default")
      (node (ref "JP3") (pin "23") (pinfunction "23_23") (pintype "passive"))
      (node (ref "U3") (pin "39") (pinfunction "TXD1_39") (pintype "passive"))
    )
    (net (code "75") (name "/E_TXD2") (class "Default")
      (node (ref "JP3") (pin "24") (pinfunction "24_24") (pintype "passive"))
      (node (ref "U3") (pin "40") (pinfunction "TXD2_40") (pintype "passive"))
    )
    (net (code "76") (name "/E_TXD3") (class "Default")
      (node (ref "JP3") (pin "25") (pinfunction "25_25") (pintype "passive"))
      (node (ref "U3") (pin "41") (pinfunction "TXD3_41") (pintype "passive"))
    )
    (net (code "77") (name "/E_TXD4") (class "Default")
      (node (ref "JP3") (pin "27") (pinfunction "27_27") (pintype "passive"))
      (node (ref "U3") (pin "43") (pinfunction "TXD4_43") (pintype "passive"))
    )
    (net (code "78") (name "/E_TXD5") (class "Default")
      (node (ref "JP3") (pin "28") (pinfunction "28_28") (pintype "passive"))
      (node (ref "U3") (pin "44") (pinfunction "TXD5_44") (pintype "passive"))
    )
    (net (code "79") (name "/E_TXD6") (class "Default")
      (node (ref "JP3") (pin "29") (pinfunction "29_29") (pintype "passive"))
      (node (ref "U3") (pin "45") (pinfunction "TXD6_45") (pintype "passive"))
    )
    (net (code "80") (name "/E_TXD7") (class "Default")
      (node (ref "JP3") (pin "30") (pinfunction "30_30") (pintype "passive"))
      (node (ref "U3") (pin "46") (pinfunction "TXD7_46") (pintype "passive"))
    )
    (net (code "81") (name "/E_TXEN") (class "Default")
      (node (ref "JP3") (pin "21") (pinfunction "21_21") (pintype "passive"))
      (node (ref "R21") (pin "2") (pinfunction "2_2") (pintype "passive"))
      (node (ref "U3") (pin "35") (pinfunction "TXEN_35") (pintype "passive"))
    )
    (net (code "82") (name "/E_TXER") (class "Default")
      (node (ref "JP3") (pin "31") (pinfunction "31_31") (pintype "passive"))
      (node (ref "U3") (pin "47") (pinfunction "TXER_47") (pintype "passive"))
    )
    (net (code "83") (name "/LED0{slash}SPISB") (class "Default")
      (node (ref "RJ？") (pin "12") (pinfunction "LED2-_12") (pintype "passive"))
      (node (ref "U1") (pin "15") (pinfunction "LED0/SPICSB_15") (pintype "passive"))
      (node (ref "U2") (pin "1") (pinfunction "CS#_1") (pintype "passive"))
    )
    (net (code "84") (name "/LED1{slash}SPISCK") (class "Default")
      (node (ref "RJ？") (pin "10") (pinfunction "LED1-_10") (pintype "passive"))
      (node (ref "U1") (pin "17") (pinfunction "LED1/SPISCK_17") (pintype "passive"))
      (node (ref "U2") (pin "6") (pinfunction "SCLK_6") (pintype "passive"))
    )
    (net (code "85") (name "/LED2") (class "Default")
      (node (ref "LED2") (pin "2") (pinfunction "K_2") (pintype "passive"))
      (node (ref "U3") (pin "52") (pinfunction "LED2_52") (pintype "passive"))
    )
    (net (code "86") (name "/RX_N") (class "Default")
      (node (ref "R6") (pin "1") (pinfunction "1_1") (pintype "passive"))
      (node (ref "U1") (pin "5") (pinfunction "MDI-[1]_5") (pintype "passive"))
    )
    (net (code "87") (name "/RX_P") (class "Default")
      (node (ref "R4") (pin "1") (pinfunction "1_1") (pintype "passive"))
      (node (ref "U1") (pin "4") (pinfunction "MDI+[1]_4") (pintype "passive"))
    )
    (net (code "88") (name "/SPISDI") (class "Default")
      (node (ref "R11") (pin "1") (pinfunction "1_1") (pintype "passive"))
      (node (ref "U1") (pin "18") (pinfunction "SPISDI_18") (pintype "passive"))
      (node (ref "U2") (pin "5") (pinfunction "SO/SIO0_5") (pintype "passive"))
    )
    (net (code "89") (name "/SPISDO") (class "Default")
      (node (ref "U1") (pin "20") (pinfunction "SPISDO_20") (pintype "passive"))
      (node (ref "U2") (pin "2") (pinfunction "SO/SIO1_2") (pintype "passive"))
    )
    (net (code "90") (name "/TX_N") (class "Default")
      (node (ref "R3") (pin "1") (pinfunction "1_1") (pintype "passive"))
      (node (ref "U1") (pin "3") (pinfunction "MDI-[0]_3") (pintype "passive"))
    )
    (net (code "91") (name "/TX_P") (class "Default")
      (node (ref "R1") (pin "1") (pinfunction "1_1") (pintype "passive"))
      (node (ref "U1") (pin "2") (pinfunction "MDI+[0]_2") (pintype "passive"))
    )
    (net (code "92") (name "/USB_DM") (class "Default")
      (node (ref "U1") (pin "7") (pinfunction "D2DM_7") (pintype "passive"))
      (node (ref "USB1") (pin "2") (pinfunction "D-_2") (pintype "passive"))
    )
    (net (code "93") (name "/USB_DP") (class "Default")
      (node (ref "U1") (pin "8") (pinfunction "D2DP_8") (pintype "passive"))
      (node (ref "USB1") (pin "3") (pinfunction "D+_3") (pintype "passive"))
    )
    (net (code "94") (name "/XTAL1") (class "Default")
      (node (ref "C12") (pin "2") (pinfunction "2_2") (pintype "passive"))
      (node (ref "U1") (pin "21") (pinfunction "XTAL1_21") (pintype "passive"))
      (node (ref "X1") (pin "2") (pinfunction "2_2") (pintype "passive"))
    )
    (net (code "95") (name "/XTAL2") (class "Default")
      (node (ref "C15") (pin "2") (pinfunction "2_2") (pintype "passive"))
      (node (ref "U1") (pin "22") (pinfunction "XTAL2_22") (pintype "passive"))
      (node (ref "X1") (pin "1") (pinfunction "1_1") (pintype "passive"))
    )
    (net (code "96") (name "1V2_VDD") (class "Default")
      (node (ref "C14") (pin "1") (pinfunction "1_1") (pintype "passive"))
      (node (ref "C16") (pin "2") (pinfunction "2_2") (pintype "passive"))
      (node (ref "C17") (pin "1") (pinfunction "1_1") (pintype "passive"))
      (node (ref "C6") (pin "2") (pinfunction "2_2") (pintype "passive"))
      (node (ref "U1") (pin "16") (pinfunction "DVDD12_16") (pintype "passive"))
      (node (ref "U1") (pin "23") (pinfunction "AVDD12_23") (pintype "passive"))
      (node (ref "U1") (pin "9") (pinfunction "DVDD12_9") (pintype "passive"))
    )
    (net (code "97") (name "3V3_VDD") (class "Default")
      (node (ref "C11") (pin "1") (pinfunction "1_1") (pintype "passive"))
      (node (ref "C13") (pin "1") (pinfunction "1_1") (pintype "passive"))
      (node (ref "C18") (pin "1") (pinfunction "1_1") (pintype "passive"))
      (node (ref "C7") (pin "1") (pinfunction "1_1") (pintype "passive"))
      (node (ref "C9") (pin "2") (pinfunction "2_2") (pintype "passive"))
      (node (ref "R10") (pin "1") (pinfunction "1_1") (pintype "passive"))
      (node (ref "R11") (pin "2") (pinfunction "2_2") (pintype "passive"))
      (node (ref "R12") (pin "2") (pinfunction "2_2") (pintype "passive"))
      (node (ref "R13") (pin "1") (pinfunction "1_1") (pintype "passive"))
      (node (ref "R9") (pin "1") (pinfunction "1_1") (pintype "passive"))
      (node (ref "U1") (pin "1") (pinfunction "AVDD33_1") (pintype "passive"))
      (node (ref "U1") (pin "10") (pinfunction "AVDD33_10") (pintype "passive"))
      (node (ref "U1") (pin "13") (pinfunction "DVDD33_13") (pintype "passive"))
      (node (ref "U2") (pin "3") (pinfunction "WP#_3") (pintype "passive"))
      (node (ref "U2") (pin "7") (pinfunction "HOLD#_7") (pintype "passive"))
      (node (ref "U2") (pin "8") (pinfunction "VCC_8") (pintype "passive"))
    )
    (net (code "98") (name "5V_USB") (class "Default")
      (node (ref "C3") (pin "1") (pinfunction "1_1") (pintype "passive"))
      (node (ref "C4") (pin "1") (pinfunction "1_1") (pintype "passive"))
      (node (ref "DZ1") (pin "2") (pinfunction "K_2") (pintype "passive"))
      (node (ref "R2") (pin "1") (pinfunction "1_1") (pintype "passive"))
      (node (ref "R5") (pin "2") (pinfunction "2_2") (pintype "passive"))
      (node (ref "U1") (pin "11") (pinfunction "VDD5_11") (pintype "passive"))
    )
    (net (code "99") (name "A1V0") (class "Default")
      (node (ref "C31") (pin "2") (pinfunction "2_2") (pintype "passive"))
      (node (ref "C32") (pin "2") (pinfunction "2_2") (pintype "passive"))
      (node (ref "C33") (pin "2") (pinfunction "2_2") (pintype "passive"))
      (node (ref "R16") (pin "2") (pinfunction "2_2") (pintype "passive"))
      (node (ref "U3") (pin "13") (pinfunction "AVDD10_13") (pintype "passive"))
      (node (ref "U3") (pin "59") (pinfunction "AVDD10_59") (pintype "passive"))
      (node (ref "U3") (pin "7") (pinfunction "AVDD10_7") (pintype "passive"))
    )
    (net (code "100") (name "AGND") (class "Default")
      (node (ref "C19") (pin "1") (pinfunction "1_1") (pintype "passive"))
      (node (ref "C20") (pin "1") (pinfunction "1_1") (pintype "passive"))
      (node (ref "C21") (pin "1") (pinfunction "1_1") (pintype "passive"))
      (node (ref "C22") (pin "1") (pinfunction "1_1") (pintype "passive"))
      (node (ref "C23") (pin "1") (pinfunction "1_1") (pintype "passive"))
      (node (ref "C24") (pin "1") (pinfunction "1_1") (pintype "passive"))
      (node (ref "C25") (pin "1") (pinfunction "1_1") (pintype "passive"))
      (node (ref "C26") (pin "1") (pinfunction "1_1") (pintype "passive"))
      (node (ref "C27") (pin "1") (pinfunction "1_1") (pintype "passive"))
      (node (ref "C28") (pin "1") (pinfunction "1_1") (pintype "passive"))
      (node (ref "C29") (pin "1") (pinfunction "1_1") (pintype "passive"))
      (node (ref "C30") (pin "1") (pinfunction "1_1") (pintype "passive"))
      (node (ref "C31") (pin "1") (pinfunction "1_1") (pintype "passive"))
      (node (ref "C32") (pin "1") (pinfunction "1_1") (pintype "passive"))
      (node (ref "C33") (pin "1") (pinfunction "1_1") (pintype "passive"))
      (node (ref "C34") (pin "1") (pinfunction "1_1") (pintype "passive"))
      (node (ref "C35") (pin "1") (pinfunction "1_1") (pintype "passive"))
      (node (ref "C38") (pin "2") (pinfunction "2_2") (pintype "passive"))
      (node (ref "C39") (pin "2") (pinfunction "2_2") (pintype "passive"))
      (node (ref "C40") (pin "2") (pinfunction "2_2") (pintype "passive"))
      (node (ref "C41") (pin "2") (pinfunction "2_2") (pintype "passive"))
      (node (ref "C42") (pin "2") (pinfunction "2_2") (pintype "passive"))
      (node (ref "JP2") (pin "3") (pinfunction "3_3") (pintype "passive"))
      (node (ref "JP3") (pin "5") (pinfunction "5_5") (pintype "passive"))
      (node (ref "JP3") (pin "6") (pinfunction "6_6") (pintype "passive"))
      (node (ref "R17") (pin "1") (pinfunction "1_1") (pintype "passive"))
      (node (ref "R18") (pin "1") (pinfunction "1_1") (pintype "passive"))
      (node (ref "R21") (pin "1") (pinfunction "1_1") (pintype "passive"))
      (node (ref "R29") (pin "1") (pinfunction "1_1") (pintype "passive"))
      (node (ref "U3") (pin "2") (pinfunction "GND_2") (pintype "passive"))
      (node (ref "U3") (pin "4") (pinfunction "GND_4") (pintype "passive"))
      (node (ref "U3") (pin "63") (pinfunction "GND_63") (pintype "passive"))
      (node (ref "U3") (pin "65") (pinfunction "EGND_65") (pintype "passive"))
      (node (ref "V1") (pin "1") (pinfunction "GND_1") (pintype "passive"))
    )
    (net (code "101") (name "D1V0") (class "Default")
      (node (ref "C23") (pin "2") (pinfunction "2_2") (pintype "passive"))
      (node (ref "C34") (pin "2") (pinfunction "2_2") (pintype "passive"))
      (node (ref "C35") (pin "2") (pinfunction "2_2") (pintype "passive"))
      (node (ref "L1") (pin "2") (pinfunction "2_2") (pintype "passive"))
      (node (ref "R16") (pin "1") (pinfunction "1_1") (pintype "passive"))
      (node (ref "U3") (pin "33") (pinfunction "DVDD10_33") (pintype "passive"))
      (node (ref "U3") (pin "48") (pinfunction "DVDD10_48") (pintype "passive"))
    )
    (net (code "102") (name "D3V3") (class "Default")
      (node (ref "C21") (pin "2") (pinfunction "2_2") (pintype "passive"))
      (node (ref "C22") (pin "2") (pinfunction "2_2") (pintype "passive"))
      (node (ref "C25") (pin "2") (pinfunction "2_2") (pintype "passive"))
      (node (ref "C26") (pin "2") (pinfunction "2_2") (pintype "passive"))
      (node (ref "C27") (pin "2") (pinfunction "2_2") (pintype "passive"))
      (node (ref "C28") (pin "2") (pinfunction "2_2") (pintype "passive"))
      (node (ref "C29") (pin "2") (pinfunction "2_2") (pintype "passive"))
      (node (ref "C30") (pin "2") (pinfunction "2_2") (pintype "passive"))
      (node (ref "JP2") (pin "1") (pinfunction "1_1") (pintype "passive"))
      (node (ref "JP3") (pin "3") (pinfunction "3_3") (pintype "passive"))
      (node (ref "JP3") (pin "4") (pinfunction "4_4") (pintype "passive"))
      (node (ref "R15") (pin "1") (pinfunction "1_1") (pintype "passive"))
      (node (ref "R23") (pin "1") (pinfunction "1_1") (pintype "passive"))
      (node (ref "R24") (pin "1") (pinfunction "1_1") (pintype "passive"))
      (node (ref "R25") (pin "1") (pinfunction "1_1") (pintype "passive"))
      (node (ref "R26") (pin "1") (pinfunction "1_1") (pintype "passive"))
      (node (ref "R28") (pin "1") (pinfunction "1_1") (pintype "passive"))
      (node (ref "R30") (pin "1") (pinfunction "1_1") (pintype "passive"))
      (node (ref "RJ1") (pin "14") (pinfunction "14_14") (pintype "passive"))
      (node (ref "U3") (pin "10") (pinfunction "AVDD33_10") (pintype "passive"))
      (node (ref "U3") (pin "20") (pinfunction "DVDD33_20") (pintype "passive"))
      (node (ref "U3") (pin "26") (pinfunction "DVDD33_26") (pintype "passive"))
      (node (ref "U3") (pin "37") (pinfunction "DVDD33_37") (pintype "passive"))
      (node (ref "U3") (pin "49") (pinfunction "DVDD33_49") (pintype "passive"))
      (node (ref "U3") (pin "60") (pinfunction "AVDD33_60") (pintype "passive"))
      (node (ref "U3") (pin "64") (pinfunction "VDDREG_64") (pintype "passive"))
      (node (ref "V1") (pin "2") (pinfunction "Vout_2") (pintype "passive"))
    )
    (net (code "103") (name "DGND") (class "Default")
      (node (ref "C19") (pin "2") (pinfunction "2_2") (pintype "passive"))
      (node (ref "C24") (pin "2") (pinfunction "2_2") (pintype "passive"))
      (node (ref "C36") (pin "2") (pinfunction "2_2") (pintype "passive"))
      (node (ref "C37") (pin "2") (pinfunction "2_2") (pintype "passive"))
      (node (ref "R17") (pin "2") (pinfunction "2_2") (pintype "passive"))
      (node (ref "R18") (pin "2") (pinfunction "2_2") (pintype "passive"))
      (node (ref "RJ1") (pin "12") (pinfunction "12_12") (pintype "passive"))
      (node (ref "RJ1") (pin "P10") (pinfunction "P10_P10") (pintype "passive"))
      (node (ref "RJ1") (pin "SHIELD0") (pinfunction "SHIELD0_SHIELD0") (pintype "passive"))
      (node (ref "RJ1") (pin "SHIELD1") (pinfunction "SHIELD1_SHIELD1") (pintype "passive"))
    )
    (net (code "104") (name "GND") (class "Default")
      (node (ref "C1") (pin "2") (pinfunction "2_2") (pintype "passive"))
      (node (ref "C10") (pin "2") (pinfunction "2_2") (pintype "passive"))
      (node (ref "C11") (pin "2") (pinfunction "2_2") (pintype "passive"))
      (node (ref "C12") (pin "1") (pinfunction "1_1") (pintype "passive"))
      (node (ref "C13") (pin "2") (pinfunction "2_2") (pintype "passive"))
      (node (ref "C14") (pin "2") (pinfunction "2_2") (pintype "passive"))
      (node (ref "C15") (pin "1") (pinfunction "1_1") (pintype "passive"))
      (node (ref "C16") (pin "1") (pinfunction "1_1") (pintype "passive"))
      (node (ref "C17") (pin "2") (pinfunction "2_2") (pintype "passive"))
      (node (ref "C18") (pin "2") (pinfunction "2_2") (pintype "passive"))
      (node (ref "C2") (pin "1") (pinfunction "1_1") (pintype "passive"))
      (node (ref "C3") (pin "2") (pinfunction "2_2") (pintype "passive"))
      (node (ref "C4") (pin "2") (pinfunction "2_2") (pintype "passive"))
      (node (ref "C5") (pin "1") (pinfunction "1_1") (pintype "passive"))
      (node (ref "C6") (pin "1") (pinfunction "1_1") (pintype "passive"))
      (node (ref "C7") (pin "2") (pinfunction "2_2") (pintype "passive"))
      (node (ref "C8") (pin "2") (pinfunction "2_2") (pintype "passive"))
      (node (ref "C9") (pin "1") (pinfunction "1_1") (pintype "passive"))
      (node (ref "DZ1") (pin "1") (pinfunction "A_1") (pintype "passive"))
      (node (ref "LED1") (pin "2") (pinfunction "K_2") (pintype "passive"))
      (node (ref "R14") (pin "2") (pinfunction "2_2") (pintype "passive"))
      (node (ref "R7") (pin "1") (pinfunction "1_1") (pintype "passive"))
      (node (ref "R8") (pin "1") (pinfunction "1_1") (pintype "passive"))
      (node (ref "U1") (pin "25") (pinfunction "GND_25") (pintype "passive"))
      (node (ref "U1") (pin "6") (pinfunction "U2GND_6") (pintype "passive"))
      (node (ref "U2") (pin "4") (pinfunction "GND_4") (pintype "passive"))
      (node (ref "USB1") (pin "4") (pinfunction "GND_4") (pintype "passive"))
    )
    (net (code "105") (name "GND-1") (class "Default")
      (node (ref "J1") (pin "A") (pinfunction "A_A") (pintype "passive"))
      (node (ref "J1") (pin "B") (pinfunction "B_B") (pintype "passive"))
    )
    (net (code "106") (name "GNDF") (class "Default")
      (node (ref "C2") (pin "2") (pinfunction "2_2") (pintype "passive"))
      (node (ref "C5") (pin "2") (pinfunction "2_2") (pintype "passive"))
      (node (ref "R7") (pin "2") (pinfunction "2_2") (pintype "passive"))
      (node (ref "R8") (pin "2") (pinfunction "2_2") (pintype "passive"))
      (node (ref "RJ？") (pin "7") (pinfunction "NC_7") (pintype "passive"))
      (node (ref "RJ？") (pin "8") (pinfunction "CHSGND_8") (pintype "passive"))
    )
    (net (code "107") (name "Net-(C1-Pad1)") (class "Default")
      (node (ref "C1") (pin "1") (pinfunction "1_1") (pintype "passive"))
      (node (ref "RJ？") (pin "4") (pintype "passive"))
      (node (ref "RJ？") (pin "5") (pintype "passive"))
    )
    (net (code "108") (name "Net-(C36-Pad1)") (class "Default")
      (node (ref "C36") (pin "1") (pinfunction "1_1") (pintype "passive"))
      (node (ref "C37") (pin "1") (pinfunction "1_1") (pintype "passive"))
      (node (ref "RJ1") (pin "P1") (pinfunction "P1_P1") (pintype "passive"))
    )
    (net (code "109") (name "Net-(JP2-Pad2)") (class "Default")
      (node (ref "JP2") (pin "2") (pinfunction "2_2") (pintype "passive"))
      (node (ref "R27") (pin "1") (pinfunction "1_1") (pintype "passive"))
    )
    (net (code "110") (name "Net-(LED1-A)") (class "Default")
      (node (ref "LED1") (pin "1") (pinfunction "A_1") (pintype "passive"))
      (node (ref "R2") (pin "2") (pinfunction "2_2") (pintype "passive"))
    )
    (net (code "111") (name "Net-(LED2-A)") (class "Default")
      (node (ref "LED2") (pin "1") (pinfunction "A_1") (pintype "passive"))
      (node (ref "R15") (pin "2") (pinfunction "2_2") (pintype "passive"))
    )
    (net (code "112") (name "Net-(RJ？-LED1+)") (class "Default")
      (node (ref "R9") (pin "2") (pinfunction "2_2") (pintype "passive"))
      (node (ref "RJ？") (pin "9") (pinfunction "LED1+_9") (pintype "passive"))
    )
    (net (code "113") (name "Net-(RJ？-LED2+)") (class "Default")
      (node (ref "R10") (pin "2") (pinfunction "2_2") (pintype "passive"))
      (node (ref "RJ？") (pin "11") (pinfunction "LED2+_11") (pintype "passive"))
    )
    (net (code "114") (name "Net-(RJ？-RD+)") (class "Default")
      (node (ref "R4") (pin "2") (pinfunction "2_2") (pintype "passive"))
      (node (ref "RJ？") (pin "3") (pinfunction "RD+_3") (pintype "passive"))
    )
    (net (code "115") (name "Net-(RJ？-RD-)") (class "Default")
      (node (ref "R6") (pin "2") (pinfunction "2_2") (pintype "passive"))
      (node (ref "RJ？") (pin "6") (pinfunction "RD-_6") (pintype "passive"))
    )
    (net (code "116") (name "Net-(RJ？-TD+)") (class "Default")
      (node (ref "R1") (pin "2") (pinfunction "2_2") (pintype "passive"))
      (node (ref "RJ？") (pin "1") (pinfunction "TD+_1") (pintype "passive"))
    )
    (net (code "117") (name "Net-(RJ？-TD-)") (class "Default")
      (node (ref "R3") (pin "2") (pinfunction "2_2") (pintype "passive"))
      (node (ref "RJ？") (pin "2") (pinfunction "TD-_2") (pintype "passive"))
    )
    (net (code "118") (name "Net-(U1-DVDD12_UPS)") (class "Default")
      (node (ref "C10") (pin "1") (pinfunction "1_1") (pintype "passive"))
      (node (ref "C8") (pin "1") (pinfunction "1_1") (pintype "passive"))
      (node (ref "U1") (pin "12") (pinfunction "DVDD12_UPS_12") (pintype "passive"))
    )
    (net (code "119") (name "Net-(U1-GPIO)") (class "Default")
      (node (ref "R12") (pin "1") (pinfunction "1_1") (pintype "passive"))
      (node (ref "U1") (pin "14") (pinfunction "GPIO_14") (pintype "passive"))
    )
    (net (code "120") (name "Net-(U1-LANWAKEB)") (class "Default")
      (node (ref "R13") (pin "2") (pinfunction "2_2") (pintype "passive"))
      (node (ref "U1") (pin "19") (pinfunction "LANWAKEB_19") (pintype "passive"))
    )
    (net (code "121") (name "Net-(U1-RSET)") (class "Default")
      (node (ref "R14") (pin "1") (pinfunction "1_1") (pintype "passive"))
      (node (ref "U1") (pin "24") (pinfunction "RSET_24") (pintype "passive"))
    )
    (net (code "122") (name "Net-(U3-CKXTAL1)") (class "Default")
      (node (ref "C41") (pin "1") (pinfunction "1_1") (pintype "passive"))
      (node (ref "U3") (pin "61") (pinfunction "CKXTAL1_61") (pintype "passive"))
      (node (ref "X2") (pin "1") (pinfunction "1_1") (pintype "passive"))
    )
    (net (code "123") (name "Net-(U3-CKXTAL2)") (class "Default")
      (node (ref "C40") (pin "1") (pinfunction "1_1") (pintype "passive"))
      (node (ref "U3") (pin "62") (pinfunction "CKXTAL2_62") (pintype "passive"))
      (node (ref "X2") (pin "2") (pinfunction "2_2") (pintype "passive"))
    )
    (net (code "124") (name "Net-(U3-INTB)") (class "Default")
      (node (ref "R30") (pin "2") (pinfunction "2_2") (pintype "passive"))
      (node (ref "U3") (pin "56") (pinfunction "INTB_56") (pintype "passive"))
    )
    (net (code "125") (name "Net-(U3-LED0{slash}PHY_AD0)") (class "Default")
      (node (ref "R20") (pin "1") (pinfunction "1_1") (pintype "passive"))
      (node (ref "U3") (pin "50") (pinfunction "LED0/PHY_AD0_50") (pintype "passive"))
    )
    (net (code "126") (name "Net-(U3-LED1{slash}PHY_AD1)") (class "Default")
      (node (ref "R22") (pin "1") (pinfunction "1_1") (pintype "passive"))
      (node (ref "U3") (pin "51") (pinfunction "LED1/PHY_AD1_51") (pintype "passive"))
    )
    (net (code "127") (name "Net-(U3-RSET)") (class "Default")
      (node (ref "R29") (pin "2") (pinfunction "2_2") (pintype "passive"))
      (node (ref "U3") (pin "58") (pinfunction "RSET_58") (pintype "passive"))
    )
    (net (code "128") (name "Net-(U3-TXCLK)") (class "Default")
      (node (ref "R19") (pin "2") (pinfunction "2_2") (pintype "passive"))
      (node (ref "U3") (pin "42") (pinfunction "TXCLK_42") (pintype "passive"))
    )
    (net (code "129") (name "Net-(USB1-VCC)") (class "Default")
      (node (ref "R5") (pin "1") (pinfunction "1_1") (pintype "passive"))
      (node (ref "USB1") (pin "1") (pinfunction "VCC_1") (pintype "passive"))
    )
    (net (code "130") (name "REG_1V0") (class "Default")
      (node (ref "L1") (pin "1") (pinfunction "1_1") (pintype "passive"))
      (node (ref "U3") (pin "3") (pinfunction "REG_OUT_3") (pintype "passive"))
    )
    (net (code "131") (name "unconnected-(SP1-Pad1)") (class "Default")
      (node (ref "SP1") (pin "1") (pinfunction "1_1") (pintype "passive"))
    )
    (net (code "132") (name "unconnected-(SP2-Pad1)") (class "Default")
      (node (ref "SP2") (pin "1") (pinfunction "1_1") (pintype "passive"))
    )
    (net (code "133") (name "unconnected-(SP3-Pad1)") (class "Default")
      (node (ref "SP3") (pin "1") (pinfunction "1_1") (pintype "passive"))
    )
    (net (code "134") (name "unconnected-(SP4-Pad1)") (class "Default")
      (node (ref "SP4") (pin "1") (pinfunction "1_1") (pintype "passive"))
    )
    (net (code "135") (name "unconnected-(U3-NC-Pad16)") (class "Default")
      (node (ref "U3") (pin "16") (pinfunction "NC_16") (pintype "passive+no_connect"))
    )
    (net (code "136") (name "unconnected-(U3-NC-Pad17)") (class "Default")
      (node (ref "U3") (pin "17") (pinfunction "NC_17") (pintype "passive+no_connect"))
    )
  )
)
